# bmsMaster_can.net
KiCad netlist of a schematic drawn in Altium Designer
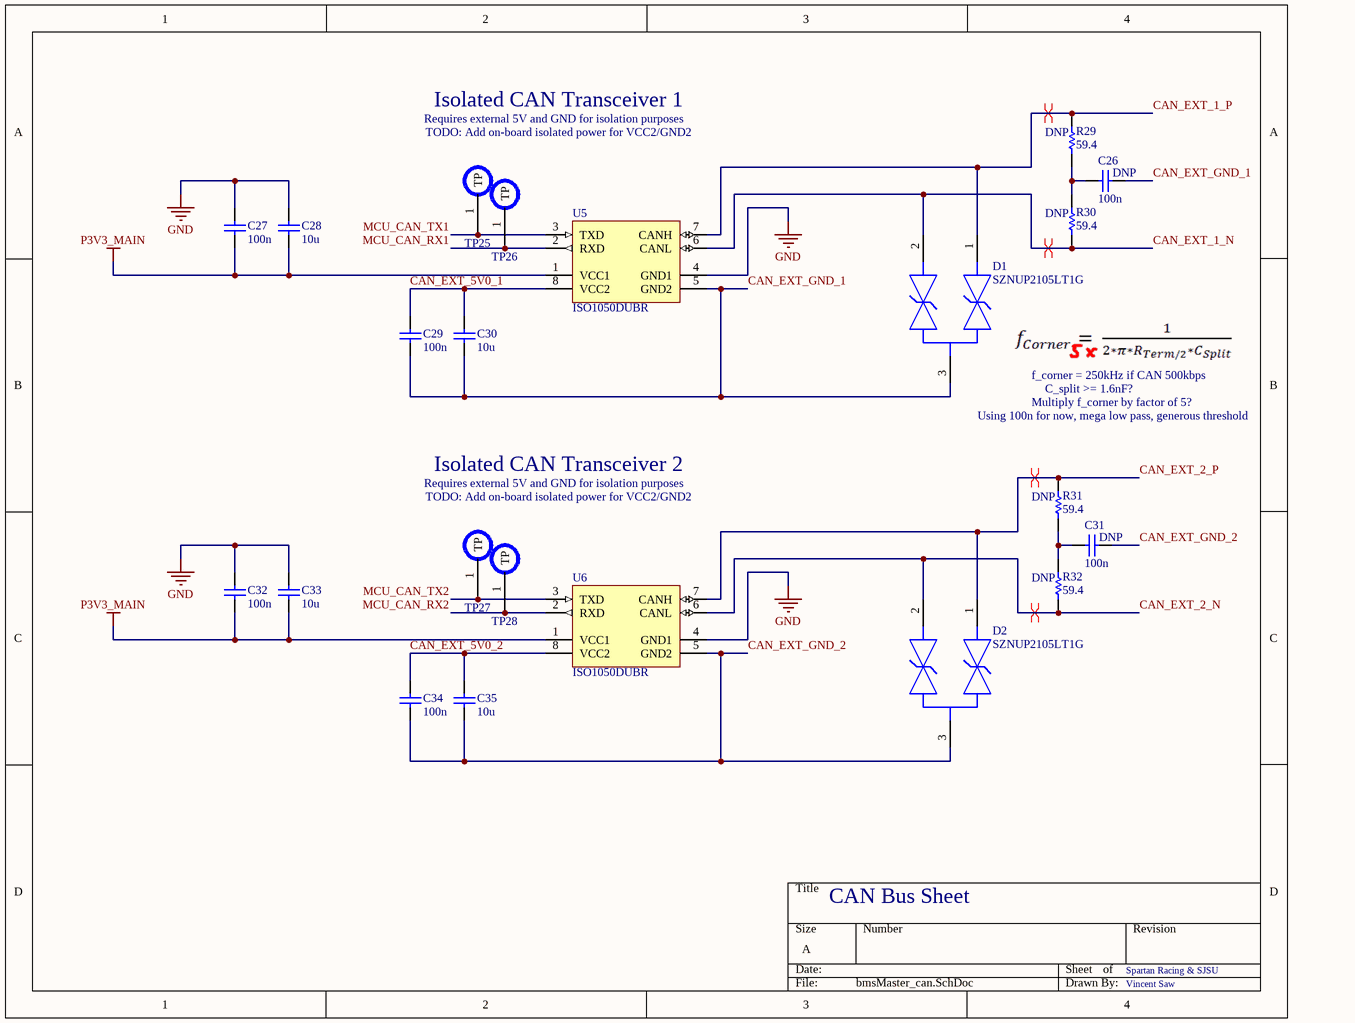
[diagram p0: bmsMaster_can.SchDoc]

(export (version "E")
  (design (tool "Eeschema 10.0.6"))
  (components
    (comp (ref "C26")
      (value "100n")
      (footprint "CAPC1608X90N")
      (description "Capacitor")
      (libsource (lib "Simulation Generic Components") (part "Capacitor"))
    )
    (comp (ref "C27")
      (value "100n")
      (footprint "CAPC1608X90N")
      (description "Capacitor")
      (libsource (lib "Simulation Generic Components") (part "Capacitor"))
    )
    (comp (ref "C28")
      (value "10u")
      (footprint "CAPC1608X90N")
      (description "Capacitor")
      (libsource (lib "Simulation Generic Components") (part "Capacitor"))
    )
    (comp (ref "C29")
      (value "100n")
      (footprint "CAPC1608X90N")
      (description "Capacitor")
      (libsource (lib "Simulation Generic Components") (part "Capacitor"))
    )
    (comp (ref "C30")
      (value "10u")
      (footprint "CAPC1608X90N")
      (description "Capacitor")
      (libsource (lib "Simulation Generic Components") (part "Capacitor"))
    )
    (comp (ref "C31")
      (value "100n")
      (footprint "CAPC1608X90N")
      (description "Capacitor")
      (libsource (lib "Simulation Generic Components") (part "Capacitor"))
    )
    (comp (ref "C32")
      (value "100n")
      (footprint "CAPC1608X90N")
      (description "Capacitor")
      (libsource (lib "Simulation Generic Components") (part "Capacitor"))
    )
    (comp (ref "C33")
      (value "10u")
      (footprint "CAPC1608X90N")
      (description "Capacitor")
      (libsource (lib "Simulation Generic Components") (part "Capacitor"))
    )
    (comp (ref "C34")
      (value "100n")
      (footprint "CAPC1608X90N")
      (description "Capacitor")
      (libsource (lib "Simulation Generic Components") (part "Capacitor"))
    )
    (comp (ref "C35")
      (value "10u")
      (footprint "CAPC1608X90N")
      (description "Capacitor")
      (libsource (lib "Simulation Generic Components") (part "Capacitor"))
    )
    (comp (ref "D1")
      (value "SZNUP2105LT1G")
      (footprint "FP-318-08-MFG")
      (description "TVS DIODE 24V 44V SOT23-3")
      (fields
        (field (name "OCTOPART") "https://octopart.com/sznup2105lt1g-on+semiconductor-22134626")
        (field (name "MANUFACTURER") "ON Semiconductor")
      )
      (libsource (lib "Altium Content Vault") (part "9fadcfe560bc2ec8fec8016e4fb2740"))
    )
    (comp (ref "D2")
      (value "SZNUP2105LT1G")
      (footprint "FP-318-08-MFG")
      (description "TVS DIODE 24V 44V SOT23-3")
      (fields
        (field (name "OCTOPART") "https://octopart.com/sznup2105lt1g-on+semiconductor-22134626")
        (field (name "MANUFACTURER") "ON Semiconductor")
      )
      (libsource (lib "Altium Content Vault") (part "9fadcfe560bc2ec8fec8016e4fb2740"))
    )
    (comp (ref "R29")
      (value "59.4")
      (footprint "RESC1608X50N")
      (description "Resistor")
      (libsource (lib "Simulation Generic Components") (part "Resistor"))
    )
    (comp (ref "R30")
      (value "59.4")
      (footprint "RESC1608X50N")
      (description "Resistor")
      (libsource (lib "Simulation Generic Components") (part "Resistor"))
    )
    (comp (ref "R31")
      (value "59.4")
      (footprint "RESC1608X50N")
      (description "Resistor")
      (libsource (lib "Simulation Generic Components") (part "Resistor"))
    )
    (comp (ref "R32")
      (value "59.4")
      (footprint "RESC1608X50N")
      (description "Resistor")
      (libsource (lib "Simulation Generic Components") (part "Resistor"))
    )
    (comp (ref "TP25")
      (value "TSTPT")
      (footprint "Testpoint1")
      (libsource (lib "testpoint1") (part "Testpoint1"))
    )
    (comp (ref "TP26")
      (value "TSTPT")
      (footprint "Testpoint1")
      (libsource (lib "testpoint1") (part "Testpoint1"))
    )
    (comp (ref "TP27")
      (value "TSTPT")
      (footprint "Testpoint1")
      (libsource (lib "testpoint1") (part "Testpoint1"))
    )
    (comp (ref "TP28")
      (value "TSTPT")
      (footprint "Testpoint1")
      (libsource (lib "testpoint1") (part "Testpoint1"))
    )
    (comp (ref "U5")
      (value "ISO1050DUBR")
      (footprint "DUB0008A_L")
      (description "Isolated CAN Transceiver, -55 to 105 degC, 8-pin SOP (DUB), Green (RoHS & no Sb/Br)")
      (fields (field (name "MANUFACTURER") "Texas Instruments"))
      (libsource (lib "Altium Content Vault") (part "TI-ISO1050-SOP_DUB-8"))
    )
    (comp (ref "U6")
      (value "ISO1050DUBR")
      (footprint "DUB0008A_L")
      (description "Isolated CAN Transceiver, -55 to 105 degC, 8-pin SOP (DUB), Green (RoHS & no Sb/Br)")
      (fields (field (name "MANUFACTURER") "Texas Instruments"))
      (libsource (lib "Altium Content Vault") (part "TI-ISO1050-SOP_DUB-8"))
    )
  )
  (nets
    (net (code "1") (name "/CAN_EXT_1_N") (class "Default")
      (node (ref "D1") (pin "2") (pinfunction "2_2") (pintype "passive"))
      (node (ref "R30") (pin "1") (pinfunction "1_1") (pintype "passive"))
      (node (ref "U5") (pin "6") (pinfunction "CANL_6") (pintype "bidirectional"))
    )
    (net (code "2") (name "/CAN_EXT_1_P") (class "Default")
      (node (ref "D1") (pin "1") (pinfunction "1_1") (pintype "passive"))
      (node (ref "R29") (pin "2") (pinfunction "2_2") (pintype "passive"))
      (node (ref "U5") (pin "7") (pinfunction "CANH_7") (pintype "bidirectional"))
    )
    (net (code "3") (name "/CAN_EXT_2_N") (class "Default")
      (node (ref "D2") (pin "2") (pinfunction "2_2") (pintype "passive"))
      (node (ref "R32") (pin "1") (pinfunction "1_1") (pintype "passive"))
      (node (ref "U6") (pin "6") (pinfunction "CANL_6") (pintype "bidirectional"))
    )
    (net (code "4") (name "/CAN_EXT_2_P") (class "Default")
      (node (ref "D2") (pin "1") (pinfunction "1_1") (pintype "passive"))
      (node (ref "R31") (pin "2") (pinfunction "2_2") (pintype "passive"))
      (node (ref "U6") (pin "7") (pinfunction "CANH_7") (pintype "bidirectional"))
    )
    (net (code "5") (name "/CAN_EXT_5V0_1") (class "Default")
      (node (ref "C29") (pin "2") (pinfunction "2_2") (pintype "passive"))
      (node (ref "C30") (pin "2") (pinfunction "2_2") (pintype "passive"))
      (node (ref "U5") (pin "8") (pinfunction "VCC2_8") (pintype "power_in"))
    )
    (net (code "6") (name "/CAN_EXT_5V0_2") (class "Default")
      (node (ref "C34") (pin "2") (pinfunction "2_2") (pintype "passive"))
      (node (ref "C35") (pin "2") (pinfunction "2_2") (pintype "passive"))
      (node (ref "U6") (pin "8") (pinfunction "VCC2_8") (pintype "power_in"))
    )
    (net (code "7") (name "/CAN_EXT_GND_1") (class "Default")
      (node (ref "C26") (pin "1") (pinfunction "1_1") (pintype "passive"))
      (node (ref "C29") (pin "1") (pinfunction "1_1") (pintype "passive"))
      (node (ref "C30") (pin "1") (pinfunction "1_1") (pintype "passive"))
      (node (ref "D1") (pin "3") (pinfunction "3_3") (pintype "passive"))
      (node (ref "U5") (pin "5") (pinfunction "GND2_5") (pintype "power_in"))
    )
    (net (code "8") (name "/CAN_EXT_GND_2") (class "Default")
      (node (ref "C31") (pin "1") (pinfunction "1_1") (pintype "passive"))
      (node (ref "C34") (pin "1") (pinfunction "1_1") (pintype "passive"))
      (node (ref "C35") (pin "1") (pinfunction "1_1") (pintype "passive"))
      (node (ref "D2") (pin "3") (pinfunction "3_3") (pintype "passive"))
      (node (ref "U6") (pin "5") (pinfunction "GND2_5") (pintype "power_in"))
    )
    (net (code "9") (name "/MCU_CAN_RX1") (class "Default")
      (node (ref "TP26") (pin "1") (pinfunction "TP_1") (pintype "passive"))
      (node (ref "U5") (pin "2") (pinfunction "RXD_2") (pintype "output"))
    )
    (net (code "10") (name "/MCU_CAN_RX2") (class "Default")
      (node (ref "TP28") (pin "1") (pinfunction "TP_1") (pintype "passive"))
      (node (ref "U6") (pin "2") (pinfunction "RXD_2") (pintype "output"))
    )
    (net (code "11") (name "/MCU_CAN_TX1") (class "Default")
      (node (ref "TP25") (pin "1") (pinfunction "TP_1") (pintype "passive"))
      (node (ref "U5") (pin "3") (pinfunction "TXD_3") (pintype "input"))
    )
    (net (code "12") (name "/MCU_CAN_TX2") (class "Default")
      (node (ref "TP27") (pin "1") (pinfunction "TP_1") (pintype "passive"))
      (node (ref "U6") (pin "3") (pinfunction "TXD_3") (pintype "input"))
    )
    (net (code "13") (name "GND") (class "Default")
      (node (ref "C27") (pin "2") (pinfunction "2_2") (pintype "passive"))
      (node (ref "C28") (pin "2") (pinfunction "2_2") (pintype "passive"))
      (node (ref "C32") (pin "2") (pinfunction "2_2") (pintype "passive"))
      (node (ref "C33") (pin "2") (pinfunction "2_2") (pintype "passive"))
      (node (ref "U5") (pin "4") (pinfunction "GND1_4") (pintype "power_in"))
      (node (ref "U6") (pin "4") (pinfunction "GND1_4") (pintype "power_in"))
    )
    (net (code "14") (name "Net-(C26-Pad2)") (class "Default")
      (node (ref "C26") (pin "2") (pinfunction "2_2") (pintype "passive"))
      (node (ref "R29") (pin "1") (pinfunction "1_1") (pintype "passive"))
      (node (ref "R30") (pin "2") (pinfunction "2_2") (pintype "passive"))
    )
    (net (code "15") (name "Net-(C31-Pad2)") (class "Default")
      (node (ref "C31") (pin "2") (pinfunction "2_2") (pintype "passive"))
      (node (ref "R31") (pin "1") (pinfunction "1_1") (pintype "passive"))
      (node (ref "R32") (pin "2") (pinfunction "2_2") (pintype "passive"))
    )
    (net (code "16") (name "P3V3_MAIN") (class "Default")
      (node (ref "C27") (pin "1") (pinfunction "1_1") (pintype "passive"))
      (node (ref "C28") (pin "1") (pinfunction "1_1") (pintype "passive"))
      (node (ref "C32") (pin "1") (pinfunction "1_1") (pintype "passive"))
      (node (ref "C33") (pin "1") (pinfunction "1_1") (pintype "passive"))
      (node (ref "U5") (pin "1") (pinfunction "VCC1_1") (pintype "power_in"))
      (node (ref "U6") (pin "1") (pinfunction "VCC1_1") (pintype "power_in"))
    )
  )
)
